# POWER.net
KiCad netlist of a schematic drawn in Altium Designer
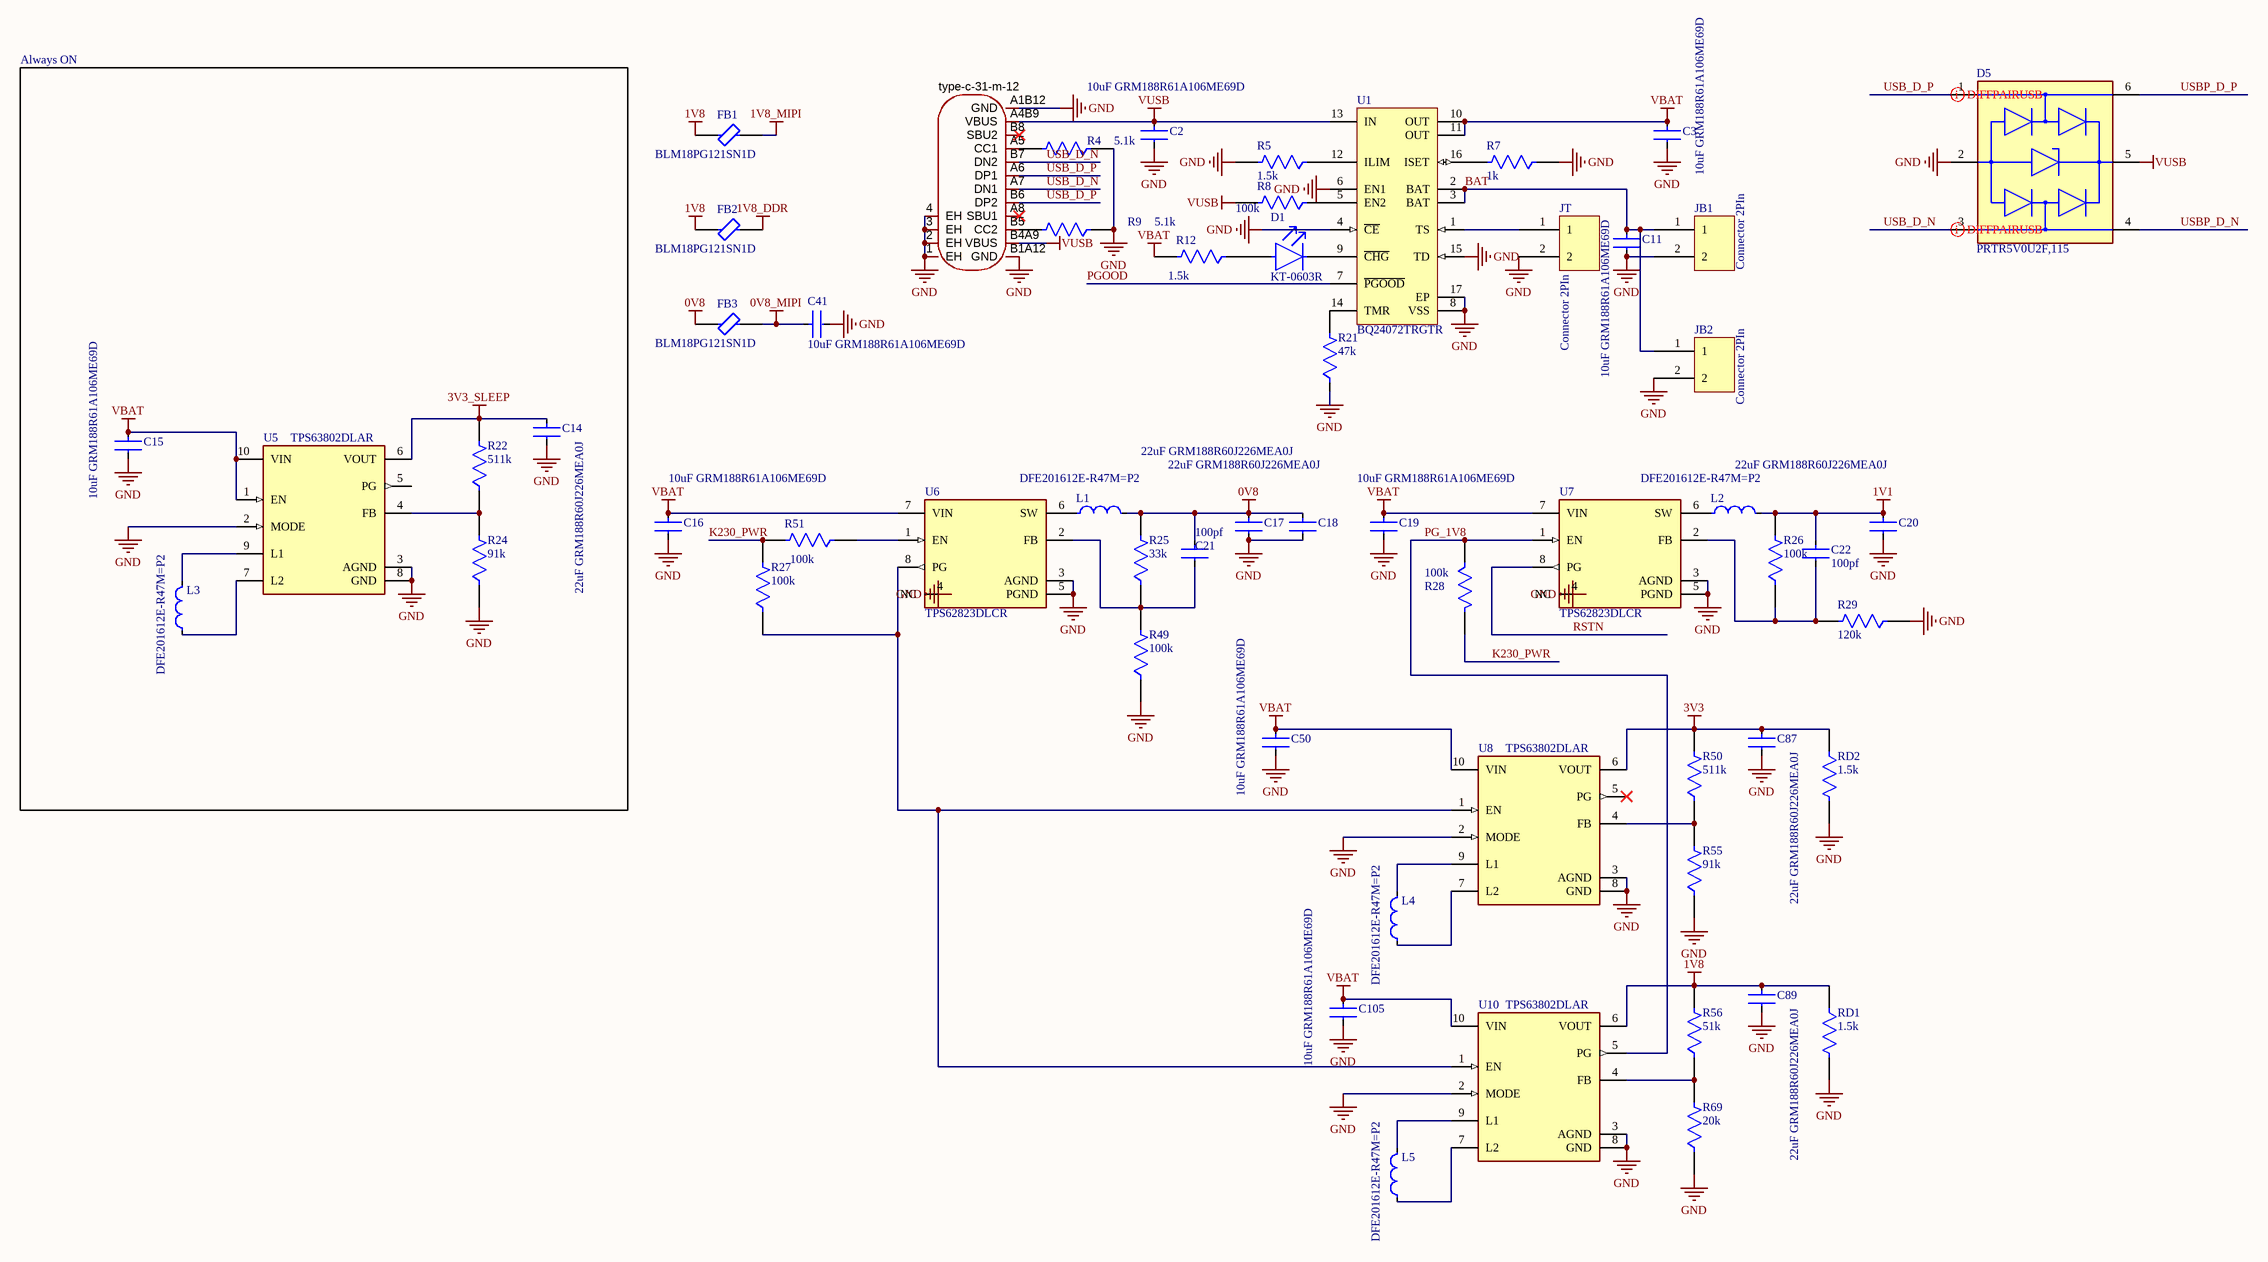
[diagram p0: POWER.SchDoc]

(export (version "E")
  (design (tool "Eeschema 10.0.6"))
  (components
    (comp (ref "C2")
      (value "10uF GRM188R61A106ME69D")
      (footprint "FP-GRM188-0_15-MFG")
      (description "C19702")
      (fields (field (name "TOLERANCE") "20%"))
      (libsource (lib "LEAKCAM") (part "CMP-06035-003612-1"))
    )
    (comp (ref "C3")
      (value "10uF GRM188R61A106ME69D")
      (footprint "FP-GRM188-0_15-MFG")
      (description "C19702")
      (fields (field (name "TOLERANCE") "20%"))
      (libsource (lib "LEAKCAM") (part "CMP-06035-003612-1"))
    )
    (comp (ref "C11")
      (value "10uF GRM188R61A106ME69D")
      (footprint "FP-GRM188-0_15-MFG")
      (description "C19702")
      (fields (field (name "TOLERANCE") "20%"))
      (libsource (lib "LEAKCAM") (part "CMP-06035-003612-1"))
    )
    (comp (ref "C14")
      (value "22uF GRM188R60J226MEA0J")
      (footprint "FP-GRM188-0_2-IPC_C")
      (description "C59461")
      (fields (field (name "TOLERANCE") "20%"))
      (libsource (lib "LEAKCAM") (part "CMP-06035-027361-1"))
    )
    (comp (ref "C15")
      (value "10uF GRM188R61A106ME69D")
      (footprint "FP-GRM188-0_15-MFG")
      (description "C19702")
      (fields (field (name "TOLERANCE") "20%"))
      (libsource (lib "LEAKCAM") (part "CMP-06035-003612-1"))
    )
    (comp (ref "C16")
      (value "10uF GRM188R61A106ME69D")
      (footprint "FP-GRM188-0_15-MFG")
      (description "C19702")
      (fields (field (name "TOLERANCE") "20%"))
      (libsource (lib "LEAKCAM") (part "CMP-06035-003612-1"))
    )
    (comp (ref "C17")
      (value "22uF GRM188R60J226MEA0J")
      (footprint "FP-GRM188-0_2-IPC_C")
      (description "C59461")
      (fields (field (name "TOLERANCE") "20%"))
      (libsource (lib "LEAKCAM") (part "CMP-06035-027361-1"))
    )
    (comp (ref "C18")
      (value "22uF GRM188R60J226MEA0J")
      (footprint "FP-GRM188-0_2-IPC_C")
      (description "C59461")
      (fields (field (name "TOLERANCE") "20%"))
      (libsource (lib "LEAKCAM") (part "CMP-06035-027361-1"))
    )
    (comp (ref "C19")
      (value "10uF GRM188R61A106ME69D")
      (footprint "FP-GRM188-0_15-MFG")
      (description "C19702")
      (fields (field (name "TOLERANCE") "20%"))
      (libsource (lib "LEAKCAM") (part "CMP-06035-003612-1"))
    )
    (comp (ref "C20")
      (value "22uF GRM188R60J226MEA0J")
      (footprint "FP-GRM188-0_2-IPC_C")
      (description "C59461")
      (fields (field (name "TOLERANCE") "20%"))
      (libsource (lib "LEAKCAM") (part "CMP-06035-027361-1"))
    )
    (comp (ref "C21")
      (value "100pf")
      (footprint "CAP_0402")
      (description "C1546")
      (fields (field (name "TOLERANCE") "10%"))
      (libsource (lib "LEAKCAM") (part "CMP-03422-001116-1"))
    )
    (comp (ref "C22")
      (value "100pf")
      (footprint "CAP_0402")
      (description "C1546")
      (fields (field (name "TOLERANCE") "10%"))
      (libsource (lib "LEAKCAM") (part "CMP-03422-001116-1"))
    )
    (comp (ref "C41")
      (value "10uF GRM188R61A106ME69D")
      (footprint "FP-GRM188-0_15-MFG")
      (description "C19702")
      (fields (field (name "TOLERANCE") "20%"))
      (libsource (lib "LEAKCAM") (part "CMP-06035-003612-1"))
    )
    (comp (ref "C50")
      (value "10uF GRM188R61A106ME69D")
      (footprint "FP-GRM188-0_15-MFG")
      (description "C19702")
      (fields (field (name "TOLERANCE") "20%"))
      (libsource (lib "LEAKCAM") (part "CMP-06035-003612-1"))
    )
    (comp (ref "C87")
      (value "22uF GRM188R60J226MEA0J")
      (footprint "FP-GRM188-0_2-IPC_C")
      (description "C59461")
      (fields (field (name "TOLERANCE") "20%"))
      (libsource (lib "LEAKCAM") (part "CMP-06035-027361-1"))
    )
    (comp (ref "C89")
      (value "22uF GRM188R60J226MEA0J")
      (footprint "FP-GRM188-0_2-IPC_C")
      (description "C59461")
      (fields (field (name "TOLERANCE") "20%"))
      (libsource (lib "LEAKCAM") (part "CMP-06035-027361-1"))
    )
    (comp (ref "C105")
      (value "10uF GRM188R61A106ME69D")
      (footprint "FP-GRM188-0_15-MFG")
      (description "C19702")
      (fields (field (name "TOLERANCE") "20%"))
      (libsource (lib "LEAKCAM") (part "CMP-06035-003612-1"))
    )
    (comp (ref "D1")
      (value "KT-0603R")
      (footprint "FP-SML-LX0603IW-TR-MFG")
      (description "C2286")
      (libsource (lib "LEAKCAM") (part "CMP-57192-000012-1"))
    )
    (comp (ref "D5")
      (value "PRTR5V0U2F,115")
      (footprint "FP-SOT886-MFG")
      (description "C478118")
      (fields
        (field (name "OCTOPART") "https://octopart.com/prtr5v0u2f%2C115-nexperia-78741690")
        (field (name "MANUFACTURER") "Nexperia")
      )
      (libsource (lib "LEAKCAM") (part "CMP-14436-000003-1"))
    )
    (comp (ref "FB1")
      (value "BLM18PG121SN1D")
      (footprint "FP-BLM18-0_15-t0_8-IPC_B")
      (description "C14709")
      (fields (field (name "TOLERANCE") "25%"))
      (libsource (lib "LEAKCAM") (part "CMP-0686-00439-3"))
    )
    (comp (ref "FB2")
      (value "BLM18PG121SN1D")
      (footprint "FP-BLM18-0_15-t0_8-IPC_B")
      (description "C14709")
      (fields (field (name "TOLERANCE") "25%"))
      (libsource (lib "LEAKCAM") (part "CMP-0686-00439-3"))
    )
    (comp (ref "FB3")
      (value "BLM18PG121SN1D")
      (footprint "FP-BLM18-0_15-t0_8-IPC_B")
      (description "C14709")
      (fields (field (name "TOLERANCE") "25%"))
      (libsource (lib "LEAKCAM") (part "CMP-0686-00439-3"))
    )
    (comp (ref "JB1")
      (value "Connector 2PIn")
      (footprint "CON_2P")
      (libsource (lib "LEAKCAM") (part "CON2P"))
    )
    (comp (ref "JB2")
      (value "Connector 2PIn")
      (footprint "CON_2P")
      (libsource (lib "LEAKCAM") (part "CON2P"))
    )
    (comp (ref "JT") (value "Connector 2PIn") (footprint "CON_2P") (libsource (lib "LEAKCAM") (part "CON2P")))
    (comp (ref "L1")
      (value "DFE201612E-R47M=P2")
      (footprint "FP-DFE201612C-IPC_C")
      (description "C668312")
      (libsource (lib "LEAKCAM") (part "CMP-06042-012656-1"))
    )
    (comp (ref "L2")
      (value "DFE201612E-R47M=P2")
      (footprint "FP-DFE201612C-IPC_C")
      (description "C668312")
      (libsource (lib "LEAKCAM") (part "CMP-06042-012656-1"))
    )
    (comp (ref "L3")
      (value "DFE201612E-R47M=P2")
      (footprint "FP-DFE201612C-IPC_C")
      (description "C668312")
      (libsource (lib "LEAKCAM") (part "CMP-06042-012656-1"))
    )
    (comp (ref "L4")
      (value "DFE201612E-R47M=P2")
      (footprint "FP-DFE201612C-IPC_C")
      (description "C668312")
      (libsource (lib "LEAKCAM") (part "CMP-06042-012656-1"))
    )
    (comp (ref "L5")
      (value "DFE201612E-R47M=P2")
      (footprint "FP-DFE201612C-IPC_C")
      (description "C668312")
      (libsource (lib "LEAKCAM") (part "CMP-06042-012656-1"))
    )
    (comp (ref "R4")
      (value "5.1k")
      (footprint "RES_0402")
      (description "C25905")
      (fields (field (name "TOLERANCE") "1%"))
      (libsource (lib "LEAKCAM") (part "CMP-03412-016018-1"))
    )
    (comp (ref "R5")
      (value "1.5k")
      (footprint "RES_0402")
      (description "C25867")
      (fields (field (name "TOLERANCE") "1%"))
      (libsource (lib "LEAKCAM") (part "CMP-03412-016018-1"))
    )
    (comp (ref "R7")
      (value "1k")
      (footprint "RES_0402")
      (description "C11702")
      (fields (field (name "TOLERANCE") "1%"))
      (libsource (lib "LEAKCAM") (part "CMP-03412-016018-1"))
    )
    (comp (ref "R8")
      (value "100k")
      (footprint "RES_0402")
      (description "C25741")
      (fields (field (name "TOLERANCE") "1%"))
      (libsource (lib "LEAKCAM") (part "CMP-03412-016018-1"))
    )
    (comp (ref "R9")
      (value "5.1k")
      (footprint "RES_0402")
      (description "C25905")
      (fields (field (name "TOLERANCE") "1%"))
      (libsource (lib "LEAKCAM") (part "CMP-03412-016018-1"))
    )
    (comp (ref "R12")
      (value "1.5k")
      (footprint "RES_0402")
      (description "C25867")
      (fields (field (name "TOLERANCE") "1%"))
      (libsource (lib "LEAKCAM") (part "CMP-03412-016018-1"))
    )
    (comp (ref "R21")
      (value "47k")
      (footprint "RES_0402")
      (description "C25792")
      (fields (field (name "TOLERANCE") "1%"))
      (libsource (lib "LEAKCAM") (part "CMP-03412-016018-1"))
    )
    (comp (ref "R22")
      (value "511k")
      (footprint "RES_0402")
      (description "C49655223")
      (fields (field (name "TOLERANCE") "1%"))
      (libsource (lib "LEAKCAM") (part "CMP-03412-016018-1"))
    )
    (comp (ref "R24")
      (value "91k")
      (footprint "RES_0402")
      (description "C54920709")
      (fields (field (name "TOLERANCE") "1%"))
      (libsource (lib "LEAKCAM") (part "CMP-03412-016018-1"))
    )
    (comp (ref "R25")
      (value "33k")
      (footprint "RES_0402")
      (description "C25779")
      (fields (field (name "TOLERANCE") "1%"))
      (libsource (lib "LEAKCAM") (part "CMP-03412-016018-1"))
    )
    (comp (ref "R26")
      (value "100k")
      (footprint "RES_0402")
      (description "C25741")
      (fields (field (name "TOLERANCE") "1%"))
      (libsource (lib "LEAKCAM") (part "CMP-03412-016018-1"))
    )
    (comp (ref "R27")
      (value "100k")
      (footprint "RES_0402")
      (description "C25741")
      (fields (field (name "TOLERANCE") "1%"))
      (libsource (lib "LEAKCAM") (part "CMP-03412-016018-1"))
    )
    (comp (ref "R28")
      (value "100k")
      (footprint "RES_0402")
      (description "C25741")
      (fields (field (name "TOLERANCE") "1%"))
      (libsource (lib "LEAKCAM") (part "CMP-03412-016018-1"))
    )
    (comp (ref "R29")
      (value "120k")
      (footprint "RES_0402")
      (description "C25750")
      (fields (field (name "TOLERANCE") "1%"))
      (libsource (lib "LEAKCAM") (part "CMP-03412-016018-1"))
    )
    (comp (ref "R49")
      (value "100k")
      (footprint "RES_0402")
      (description "C25741")
      (fields (field (name "TOLERANCE") "1%"))
      (libsource (lib "LEAKCAM") (part "CMP-03412-016018-1"))
    )
    (comp (ref "R50")
      (value "511k")
      (footprint "RES_0402")
      (description "C49655223")
      (fields (field (name "TOLERANCE") "1%"))
      (libsource (lib "LEAKCAM") (part "CMP-03412-016018-1"))
    )
    (comp (ref "R51")
      (value "100k")
      (footprint "RES_0402")
      (description "C25741")
      (fields (field (name "TOLERANCE") "1%"))
      (libsource (lib "LEAKCAM") (part "CMP-03412-016018-1"))
    )
    (comp (ref "R55")
      (value "91k")
      (footprint "RES_0402")
      (description "C54920709")
      (fields (field (name "TOLERANCE") "1%"))
      (libsource (lib "LEAKCAM") (part "CMP-03412-016018-1"))
    )
    (comp (ref "R56")
      (value "51k")
      (footprint "RES_0402")
      (description "C25794")
      (fields (field (name "TOLERANCE") "1%"))
      (libsource (lib "LEAKCAM") (part "CMP-03412-016018-1"))
    )
    (comp (ref "R69")
      (value "20k")
      (footprint "RES_0402")
      (description "C25765")
      (fields (field (name "TOLERANCE") "1%"))
      (libsource (lib "LEAKCAM") (part "CMP-03412-016018-1"))
    )
    (comp (ref "RD1")
      (value "1.5k")
      (footprint "RES_0402")
      (description "C25867")
      (fields (field (name "TOLERANCE") "1%"))
      (libsource (lib "LEAKCAM") (part "CMP-03412-016018-1"))
    )
    (comp (ref "RD2")
      (value "1.5k")
      (footprint "RES_0402")
      (description "C25867")
      (fields (field (name "TOLERANCE") "1%"))
      (libsource (lib "LEAKCAM") (part "CMP-03412-016018-1"))
    )
    (comp (ref "U1")
      (value "BQ24072TRGTR")
      (footprint "RGT0016C_V")
      (description "C129319")
      (fields (field (name "MANUFACTURER") "Texas Instruments"))
      (libsource (lib "LEAKCAM") (part "CMP-0321-00268-2"))
    )
    (comp (ref "U5")
      (value "TPS63802DLAR")
      (footprint "FP-DLA0010A-MFG")
      (description "C2845237")
      (fields
        (field (name "OCTOPART") "https://octopart.com/tps63802dlar-texas+instruments-97359678")
        (field (name "MANUFACTURER") "Texas Instruments")
      )
      (libsource (lib "LEAKCAM") (part "CMP-04918-000005-1"))
    )
    (comp (ref "U6")
      (value "TPS62823DLCR")
      (footprint "FP-DLC0008A-MFG")
      (description "C2693497")
      (libsource (lib "LEAKCAM") (part "CMP-04918-000715-1"))
    )
    (comp (ref "U7")
      (value "TPS62823DLCR")
      (footprint "FP-DLC0008A-MFG")
      (description "C2693497")
      (libsource (lib "LEAKCAM") (part "CMP-04918-000715-1"))
    )
    (comp (ref "U8")
      (value "TPS63802DLAR")
      (footprint "FP-DLA0010A-MFG")
      (description "C2845237")
      (fields
        (field (name "OCTOPART") "https://octopart.com/tps63802dlar-texas+instruments-97359678")
        (field (name "MANUFACTURER") "Texas Instruments")
      )
      (libsource (lib "LEAKCAM") (part "CMP-04918-000005-1"))
    )
    (comp (ref "U10")
      (value "TPS63802DLAR")
      (footprint "FP-DLA0010A-MFG")
      (description "C2845237")
      (fields
        (field (name "OCTOPART") "https://octopart.com/tps63802dlar-texas+instruments-97359678")
        (field (name "MANUFACTURER") "Texas Instruments")
      )
      (libsource (lib "LEAKCAM") (part "CMP-04918-000005-1"))
    )
    (comp (ref "USBC1")
      (value "type-c-31-m-12")
      (footprint "TYPE-C-31-M-12")
      (description "C165948")
      (fields (field (name "MANUFACTURER") "韩国韩荣") (field (name "MANUFACTURERPART") "TYPE-C-31-M-12"))
      (libsource (lib "LEAKCAM") (part "type-c-31-m-12"))
    )
  )
  (nets
    (net (code "1") (name "/BAT") (class "Default")
      (node (ref "C11") (pin "1") (pinfunction "1_1") (pintype "passive"))
      (node (ref "JB1") (pin "1") (pinfunction "1_1") (pintype "passive"))
      (node (ref "JB2") (pin "1") (pinfunction "1_1") (pintype "passive"))
      (node (ref "U1") (pin "2") (pinfunction "BAT_2") (pintype "power_in"))
      (node (ref "U1") (pin "3") (pinfunction "BAT_3") (pintype "power_in"))
    )
    (net (code "2") (name "/K230_PWR") (class "Default")
      (node (ref "R27") (pin "2") (pinfunction "2_2") (pintype "passive"))
      (node (ref "R28") (pin "2") (pinfunction "2_2") (pintype "passive"))
      (node (ref "R51") (pin "2") (pinfunction "2_2") (pintype "passive"))
    )
    (net (code "3") (name "/PGOOD") (class "Default")
      (node (ref "U1") (pin "7") (pinfunction "~{PGOOD}_7") (pintype "tri_state"))
    )
    (net (code "4") (name "/PG_1V8") (class "Default")
      (node (ref "R28") (pin "1") (pinfunction "1_1") (pintype "passive"))
      (node (ref "U10") (pin "5") (pinfunction "PG_5") (pintype "output"))
      (node (ref "U7") (pin "1") (pinfunction "EN_1") (pintype "input"))
    )
    (net (code "5") (name "/RSTN") (class "Default")
      (node (ref "U7") (pin "8") (pinfunction "PG_8") (pintype "output"))
    )
    (net (code "6") (name "/USBP_D_N") (class "Default")
      (node (ref "D5") (pin "4") (pinfunction "I/O2_4") (pintype "passive"))
    )
    (net (code "7") (name "/USBP_D_P") (class "Default")
      (node (ref "D5") (pin "6") (pinfunction "I/O1_6") (pintype "passive"))
    )
    (net (code "8") (name "/USB_D_N") (class "Default")
      (node (ref "D5") (pin "3") (pinfunction "I/O2_3") (pintype "passive"))
      (node (ref "USBC1") (pin "A7") (pinfunction "DN1_A7") (pintype "passive"))
      (node (ref "USBC1") (pin "B7") (pinfunction "DN2_B7") (pintype "passive"))
    )
    (net (code "9") (name "/USB_D_P") (class "Default")
      (node (ref "D5") (pin "1") (pinfunction "I/O1_1") (pintype "passive"))
      (node (ref "USBC1") (pin "A6") (pinfunction "DP1_A6") (pintype "passive"))
      (node (ref "USBC1") (pin "B6") (pinfunction "DP2_B6") (pintype "passive"))
    )
    (net (code "10") (name "0V8") (class "Default")
      (node (ref "C17") (pin "1") (pinfunction "1_1") (pintype "passive"))
      (node (ref "C18") (pin "1") (pinfunction "1_1") (pintype "passive"))
      (node (ref "C21") (pin "1") (pinfunction "1_1") (pintype "passive"))
      (node (ref "FB3") (pin "1") (pinfunction "1_1") (pintype "passive"))
      (node (ref "L1") (pin "2") (pinfunction "2_2") (pintype "passive"))
      (node (ref "R25") (pin "2") (pinfunction "2_2") (pintype "passive"))
    )
    (net (code "11") (name "0V8_MIPI") (class "Default")
      (node (ref "C41") (pin "1") (pinfunction "1_1") (pintype "passive"))
      (node (ref "FB3") (pin "2") (pinfunction "2_2") (pintype "passive"))
    )
    (net (code "12") (name "1V1") (class "Default")
      (node (ref "C20") (pin "1") (pinfunction "1_1") (pintype "passive"))
      (node (ref "C22") (pin "1") (pinfunction "1_1") (pintype "passive"))
      (node (ref "L2") (pin "2") (pinfunction "2_2") (pintype "passive"))
      (node (ref "R26") (pin "2") (pinfunction "2_2") (pintype "passive"))
    )
    (net (code "13") (name "1V8") (class "Default")
      (node (ref "C89") (pin "1") (pinfunction "1_1") (pintype "passive"))
      (node (ref "FB1") (pin "1") (pinfunction "1_1") (pintype "passive"))
      (node (ref "FB2") (pin "1") (pinfunction "1_1") (pintype "passive"))
      (node (ref "R56") (pin "2") (pinfunction "2_2") (pintype "passive"))
      (node (ref "RD1") (pin "1") (pinfunction "1_1") (pintype "passive"))
      (node (ref "U10") (pin "6") (pinfunction "VOUT_6") (pintype "power_in"))
    )
    (net (code "14") (name "1V8_DDR") (class "Default")
      (node (ref "FB2") (pin "2") (pinfunction "2_2") (pintype "passive"))
    )
    (net (code "15") (name "1V8_MIPI") (class "Default")
      (node (ref "FB1") (pin "2") (pinfunction "2_2") (pintype "passive"))
    )
    (net (code "16") (name "3V3") (class "Default")
      (node (ref "C87") (pin "1") (pinfunction "1_1") (pintype "passive"))
      (node (ref "R50") (pin "2") (pinfunction "2_2") (pintype "passive"))
      (node (ref "RD2") (pin "1") (pinfunction "1_1") (pintype "passive"))
      (node (ref "U8") (pin "6") (pinfunction "VOUT_6") (pintype "power_in"))
    )
    (net (code "17") (name "3V3_SLEEP") (class "Default")
      (node (ref "C14") (pin "1") (pinfunction "1_1") (pintype "passive"))
      (node (ref "R22") (pin "2") (pinfunction "2_2") (pintype "passive"))
      (node (ref "U5") (pin "6") (pinfunction "VOUT_6") (pintype "power_in"))
    )
    (net (code "18") (name "GND") (class "Default")
      (node (ref "C105") (pin "2") (pinfunction "2_2") (pintype "passive"))
      (node (ref "C11") (pin "2") (pinfunction "2_2") (pintype "passive"))
      (node (ref "C14") (pin "2") (pinfunction "2_2") (pintype "passive"))
      (node (ref "C15") (pin "2") (pinfunction "2_2") (pintype "passive"))
      (node (ref "C16") (pin "2") (pinfunction "2_2") (pintype "passive"))
      (node (ref "C17") (pin "2") (pinfunction "2_2") (pintype "passive"))
      (node (ref "C18") (pin "2") (pinfunction "2_2") (pintype "passive"))
      (node (ref "C19") (pin "2") (pinfunction "2_2") (pintype "passive"))
      (node (ref "C2") (pin "2") (pinfunction "2_2") (pintype "passive"))
      (node (ref "C20") (pin "2") (pinfunction "2_2") (pintype "passive"))
      (node (ref "C3") (pin "2") (pinfunction "2_2") (pintype "passive"))
      (node (ref "C41") (pin "2") (pinfunction "2_2") (pintype "passive"))
      (node (ref "C50") (pin "2") (pinfunction "2_2") (pintype "passive"))
      (node (ref "C87") (pin "2") (pinfunction "2_2") (pintype "passive"))
      (node (ref "C89") (pin "2") (pinfunction "2_2") (pintype "passive"))
      (node (ref "D5") (pin "2") (pinfunction "GND_2") (pintype "power_in"))
      (node (ref "JB1") (pin "2") (pinfunction "2_2") (pintype "passive"))
      (node (ref "JB2") (pin "2") (pinfunction "2_2") (pintype "passive"))
      (node (ref "JT") (pin "2") (pinfunction "2_2") (pintype "passive"))
      (node (ref "R21") (pin "1") (pinfunction "1_1") (pintype "passive"))
      (node (ref "R24") (pin "1") (pinfunction "1_1") (pintype "passive"))
      (node (ref "R29") (pin "1") (pinfunction "1_1") (pintype "passive"))
      (node (ref "R4") (pin "1") (pinfunction "1_1") (pintype "passive"))
      (node (ref "R49") (pin "1") (pinfunction "1_1") (pintype "passive"))
      (node (ref "R5") (pin "2") (pinfunction "2_2") (pintype "passive"))
      (node (ref "R55") (pin "1") (pinfunction "1_1") (pintype "passive"))
      (node (ref "R69") (pin "1") (pinfunction "1_1") (pintype "passive"))
      (node (ref "R7") (pin "1") (pinfunction "1_1") (pintype "passive"))
      (node (ref "R9") (pin "1") (pinfunction "1_1") (pintype "passive"))
      (node (ref "RD1") (pin "2") (pinfunction "2_2") (pintype "passive"))
      (node (ref "RD2") (pin "2") (pinfunction "2_2") (pintype "passive"))
      (node (ref "U1") (pin "15") (pinfunction "TD_15") (pintype "input"))
      (node (ref "U1") (pin "17") (pinfunction "EP_17") (pintype "power_in"))
      (node (ref "U1") (pin "4") (pinfunction "~{CE}_4") (pintype "input"))
      (node (ref "U1") (pin "6") (pinfunction "EN1_6") (pintype "passive"))
      (node (ref "U1") (pin "8") (pinfunction "VSS_8") (pintype "power_in"))
      (node (ref "U10") (pin "2") (pinfunction "MODE_2") (pintype "input"))
      (node (ref "U10") (pin "3") (pinfunction "AGND_3") (pintype "power_in"))
      (node (ref "U10") (pin "8") (pinfunction "GND_8") (pintype "power_in"))
      (node (ref "U5") (pin "2") (pinfunction "MODE_2") (pintype "input"))
      (node (ref "U5") (pin "3") (pinfunction "AGND_3") (pintype "power_in"))
      (node (ref "U5") (pin "8") (pinfunction "GND_8") (pintype "power_in"))
      (node (ref "U6") (pin "3") (pinfunction "AGND_3") (pintype "power_in"))
      (node (ref "U6") (pin "4") (pinfunction "NC_4") (pintype "passive"))
      (node (ref "U6") (pin "5") (pinfunction "PGND_5") (pintype "power_in"))
      (node (ref "U7") (pin "3") (pinfunction "AGND_3") (pintype "power_in"))
      (node (ref "U7") (pin "4") (pinfunction "NC_4") (pintype "passive"))
      (node (ref "U7") (pin "5") (pinfunction "PGND_5") (pintype "power_in"))
      (node (ref "U8") (pin "2") (pinfunction "MODE_2") (pintype "input"))
      (node (ref "U8") (pin "3") (pinfunction "AGND_3") (pintype "power_in"))
      (node (ref "U8") (pin "8") (pinfunction "GND_8") (pintype "power_in"))
      (node (ref "USBC1") (pin "1") (pinfunction "EH_1") (pintype "passive"))
      (node (ref "USBC1") (pin "2") (pinfunction "EH_2") (pintype "passive"))
      (node (ref "USBC1") (pin "3") (pinfunction "EH_3") (pintype "passive"))
      (node (ref "USBC1") (pin "4") (pinfunction "EH_4") (pintype "passive"))
      (node (ref "USBC1") (pin "A1B12") (pinfunction "GND_A1B12") (pintype "passive"))
      (node (ref "USBC1") (pin "B1A12") (pinfunction "GND_B1A12") (pintype "passive"))
    )
    (net (code "19") (name "Net-(D1-A)") (class "Default")
      (node (ref "D1") (pin "2") (pinfunction "A_2") (pintype "passive"))
      (node (ref "R12") (pin "1") (pinfunction "1_1") (pintype "passive"))
    )
    (net (code "20") (name "Net-(D1-C)") (class "Default")
      (node (ref "D1") (pin "1") (pinfunction "C_1") (pintype "passive"))
      (node (ref "U1") (pin "9") (pinfunction "~{CHG}_9") (pintype "tri_state"))
    )
    (net (code "21") (name "Net-(U1-EN2)") (class "Default")
      (node (ref "R8") (pin "1") (pinfunction "1_1") (pintype "passive"))
      (node (ref "U1") (pin "5") (pinfunction "EN2_5") (pintype "passive"))
    )
    (net (code "22") (name "Net-(U1-ILIM)") (class "Default")
      (node (ref "R5") (pin "1") (pinfunction "1_1") (pintype "passive"))
      (node (ref "U1") (pin "12") (pinfunction "ILIM_12") (pintype "passive"))
    )
    (net (code "23") (name "Net-(U1-ISET)") (class "Default")
      (node (ref "R7") (pin "2") (pinfunction "2_2") (pintype "passive"))
      (node (ref "U1") (pin "16") (pinfunction "ISET_16") (pintype "bidirectional"))
    )
    (net (code "24") (name "Net-(U1-TMR)") (class "Default")
      (node (ref "R21") (pin "2") (pinfunction "2_2") (pintype "passive"))
      (node (ref "U1") (pin "14") (pinfunction "TMR_14") (pintype "passive"))
    )
    (net (code "25") (name "Net-(U1-TS)") (class "Default")
      (node (ref "JT") (pin "1") (pinfunction "1_1") (pintype "passive"))
      (node (ref "U1") (pin "1") (pinfunction "TS_1") (pintype "input"))
    )
    (net (code "26") (name "Net-(U5-FB)") (class "Default")
      (node (ref "R22") (pin "1") (pinfunction "1_1") (pintype "passive"))
      (node (ref "R24") (pin "2") (pinfunction "2_2") (pintype "passive"))
      (node (ref "U5") (pin "4") (pinfunction "FB_4") (pintype "passive"))
    )
    (net (code "27") (name "Net-(U5-L1)") (class "Default")
      (node (ref "L3") (pin "2") (pinfunction "2_2") (pintype "passive"))
      (node (ref "U5") (pin "9") (pinfunction "L1_9") (pintype "passive"))
    )
    (net (code "28") (name "Net-(U5-L2)") (class "Default")
      (node (ref "L3") (pin "1") (pinfunction "1_1") (pintype "passive"))
      (node (ref "U5") (pin "7") (pinfunction "L2_7") (pintype "passive"))
    )
    (net (code "29") (name "Net-(U6-EN)") (class "Default")
      (node (ref "R51") (pin "1") (pinfunction "1_1") (pintype "passive"))
      (node (ref "U6") (pin "1") (pinfunction "EN_1") (pintype "input"))
    )
    (net (code "30") (name "Net-(U6-FB)") (class "Default")
      (node (ref "C21") (pin "2") (pinfunction "2_2") (pintype "passive"))
      (node (ref "R25") (pin "1") (pinfunction "1_1") (pintype "passive"))
      (node (ref "R49") (pin "2") (pinfunction "2_2") (pintype "passive"))
      (node (ref "U6") (pin "2") (pinfunction "FB_2") (pintype "passive"))
    )
    (net (code "31") (name "Net-(U6-SW)") (class "Default")
      (node (ref "L1") (pin "1") (pinfunction "1_1") (pintype "passive"))
      (node (ref "U6") (pin "6") (pinfunction "SW_6") (pintype "power_in"))
    )
    (net (code "32") (name "Net-(U7-FB)") (class "Default")
      (node (ref "C22") (pin "2") (pinfunction "2_2") (pintype "passive"))
      (node (ref "R26") (pin "1") (pinfunction "1_1") (pintype "passive"))
      (node (ref "R29") (pin "2") (pinfunction "2_2") (pintype "passive"))
      (node (ref "U7") (pin "2") (pinfunction "FB_2") (pintype "passive"))
    )
    (net (code "33") (name "Net-(U7-SW)") (class "Default")
      (node (ref "L2") (pin "1") (pinfunction "1_1") (pintype "passive"))
      (node (ref "U7") (pin "6") (pinfunction "SW_6") (pintype "power_in"))
    )
    (net (code "34") (name "Net-(U8-FB)") (class "Default")
      (node (ref "R50") (pin "1") (pinfunction "1_1") (pintype "passive"))
      (node (ref "R55") (pin "2") (pinfunction "2_2") (pintype "passive"))
      (node (ref "U8") (pin "4") (pinfunction "FB_4") (pintype "passive"))
    )
    (net (code "35") (name "Net-(U8-L1)") (class "Default")
      (node (ref "L4") (pin "2") (pinfunction "2_2") (pintype "passive"))
      (node (ref "U8") (pin "9") (pinfunction "L1_9") (pintype "passive"))
    )
    (net (code "36") (name "Net-(U8-L2)") (class "Default")
      (node (ref "L4") (pin "1") (pinfunction "1_1") (pintype "passive"))
      (node (ref "U8") (pin "7") (pinfunction "L2_7") (pintype "passive"))
    )
    (net (code "37") (name "Net-(U10-EN)") (class "Default")
      (node (ref "R27") (pin "1") (pinfunction "1_1") (pintype "passive"))
      (node (ref "U10") (pin "1") (pinfunction "EN_1") (pintype "input"))
      (node (ref "U6") (pin "8") (pinfunction "PG_8") (pintype "output"))
      (node (ref "U8") (pin "1") (pinfunction "EN_1") (pintype "input"))
    )
    (net (code "38") (name "Net-(U10-FB)") (class "Default")
      (node (ref "R56") (pin "1") (pinfunction "1_1") (pintype "passive"))
      (node (ref "R69") (pin "2") (pinfunction "2_2") (pintype "passive"))
      (node (ref "U10") (pin "4") (pinfunction "FB_4") (pintype "passive"))
    )
    (net (code "39") (name "Net-(U10-L1)") (class "Default")
      (node (ref "L5") (pin "2") (pinfunction "2_2") (pintype "passive"))
      (node (ref "U10") (pin "9") (pinfunction "L1_9") (pintype "passive"))
    )
    (net (code "40") (name "Net-(U10-L2)") (class "Default")
      (node (ref "L5") (pin "1") (pinfunction "1_1") (pintype "passive"))
      (node (ref "U10") (pin "7") (pinfunction "L2_7") (pintype "passive"))
    )
    (net (code "41") (name "Net-(USBC1-CC1)") (class "Default")
      (node (ref "R4") (pin "2") (pinfunction "2_2") (pintype "passive"))
      (node (ref "USBC1") (pin "A5") (pinfunction "CC1_A5") (pintype "passive"))
    )
    (net (code "42") (name "Net-(USBC1-CC2)") (class "Default")
      (node (ref "R9") (pin "2") (pinfunction "2_2") (pintype "passive"))
      (node (ref "USBC1") (pin "B5") (pinfunction "CC2_B5") (pintype "passive"))
    )
    (net (code "43") (name "VBAT") (class "Default")
      (node (ref "C105") (pin "1") (pinfunction "1_1") (pintype "passive"))
      (node (ref "C15") (pin "1") (pinfunction "1_1") (pintype "passive"))
      (node (ref "C16") (pin "1") (pinfunction "1_1") (pintype "passive"))
      (node (ref "C19") (pin "1") (pinfunction "1_1") (pintype "passive"))
      (node (ref "C3") (pin "1") (pinfunction "1_1") (pintype "passive"))
      (node (ref "C50") (pin "1") (pinfunction "1_1") (pintype "passive"))
      (node (ref "R12") (pin "2") (pinfunction "2_2") (pintype "passive"))
      (node (ref "U1") (pin "10") (pinfunction "OUT_10") (pintype "power_in"))
      (node (ref "U1") (pin "11") (pinfunction "OUT_11") (pintype "power_in"))
      (node (ref "U10") (pin "10") (pinfunction "VIN_10") (pintype "power_in"))
      (node (ref "U5") (pin "1") (pinfunction "EN_1") (pintype "input"))
      (node (ref "U5") (pin "10") (pinfunction "VIN_10") (pintype "power_in"))
      (node (ref "U6") (pin "7") (pinfunction "VIN_7") (pintype "power_in"))
      (node (ref "U7") (pin "7") (pinfunction "VIN_7") (pintype "power_in"))
      (node (ref "U8") (pin "10") (pinfunction "VIN_10") (pintype "power_in"))
    )
    (net (code "44") (name "VUSB") (class "Default")
      (node (ref "C2") (pin "1") (pinfunction "1_1") (pintype "passive"))
      (node (ref "D5") (pin "5") (pinfunction "VCC_5") (pintype "power_in"))
      (node (ref "R8") (pin "2") (pinfunction "2_2") (pintype "passive"))
      (node (ref "U1") (pin "13") (pinfunction "IN_13") (pintype "power_in"))
      (node (ref "USBC1") (pin "A4B9") (pinfunction "VBUS_A4B9") (pintype "passive"))
      (node (ref "USBC1") (pin "B4A9") (pinfunction "VBUS_B4A9") (pintype "passive"))
    )
    (net (code "45") (name "unconnected-(U5-PG-Pad5)") (class "Default")
      (node (ref "U5") (pin "5") (pinfunction "PG_5") (pintype "output"))
    )
    (net (code "46") (name "unconnected-(U8-PG-Pad5)") (class "Default")
      (node (ref "U8") (pin "5") (pinfunction "PG_5") (pintype "output+no_connect"))
    )
    (net (code "47") (name "unconnected-(USBC1-SBU1-PadA8)") (class "Default")
      (node (ref "USBC1") (pin "A8") (pinfunction "SBU1_A8") (pintype "passive+no_connect"))
    )
    (net (code "48") (name "unconnected-(USBC1-SBU2-PadB8)") (class "Default")
      (node (ref "USBC1") (pin "B8") (pinfunction "SBU2_B8") (pintype "passive+no_connect"))
    )
  )
)
